# braille_keyboard.net
KiCad netlist of a schematic drawn in EAGLE
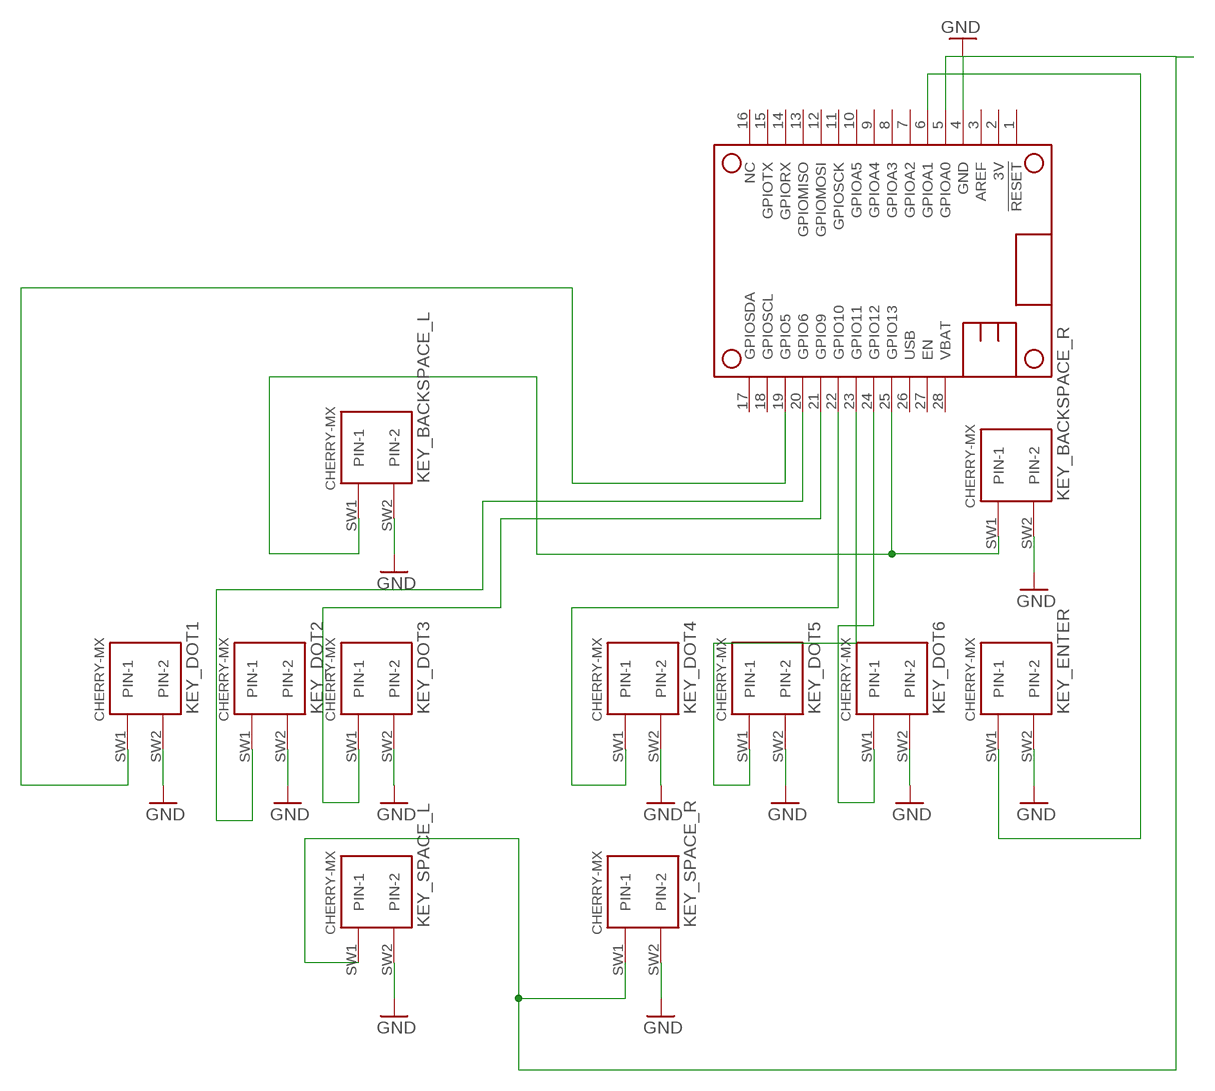
[diagram p0: schematic, sheet 1]

(export (version "E")
  (design (tool "Eeschema 10.0.6"))
  (components
    (comp (ref "KEY_BACKSPACE_L")
      (value "CHERRY-MX")
      (footprint "eagle-import:CHERRY-MX")
      (libsource (lib "eagle-import") (part "CHERRY-MX"))
    )
    (comp (ref "KEY_BACKSPACE_R")
      (value "CHERRY-MX")
      (footprint "eagle-import:CHERRY-MX")
      (libsource (lib "eagle-import") (part "CHERRY-MX"))
    )
    (comp (ref "KEY_DOT1")
      (value "CHERRY-MX")
      (footprint "eagle-import:CHERRY-MX")
      (libsource (lib "eagle-import") (part "CHERRY-MX"))
    )
    (comp (ref "KEY_DOT2")
      (value "CHERRY-MX")
      (footprint "eagle-import:CHERRY-MX")
      (libsource (lib "eagle-import") (part "CHERRY-MX"))
    )
    (comp (ref "KEY_DOT3")
      (value "CHERRY-MX")
      (footprint "eagle-import:CHERRY-MX")
      (libsource (lib "eagle-import") (part "CHERRY-MX"))
    )
    (comp (ref "KEY_DOT4")
      (value "CHERRY-MX")
      (footprint "eagle-import:CHERRY-MX")
      (libsource (lib "eagle-import") (part "CHERRY-MX"))
    )
    (comp (ref "KEY_DOT5")
      (value "CHERRY-MX")
      (footprint "eagle-import:CHERRY-MX")
      (libsource (lib "eagle-import") (part "CHERRY-MX"))
    )
    (comp (ref "KEY_DOT6")
      (value "CHERRY-MX")
      (footprint "eagle-import:CHERRY-MX")
      (libsource (lib "eagle-import") (part "CHERRY-MX"))
    )
    (comp (ref "KEY_ENTER")
      (value "CHERRY-MX")
      (footprint "eagle-import:CHERRY-MX")
      (libsource (lib "eagle-import") (part "CHERRY-MX"))
    )
    (comp (ref "KEY_SPACE_L")
      (value "CHERRY-MX")
      (footprint "eagle-import:CHERRY-MX")
      (libsource (lib "eagle-import") (part "CHERRY-MX"))
    )
    (comp (ref "KEY_SPACE_R")
      (value "CHERRY-MX")
      (footprint "eagle-import:CHERRY-MX")
      (libsource (lib "eagle-import") (part "CHERRY-MX"))
    )
    (comp (ref "MS1")
      (value "FEATHERWING")
      (footprint "eagle-import:FEATHERWING")
      (libsource (lib "eagle-import") (part "FEATHERWING"))
    )
  )
  (nets
    (net (code "1") (name "/3V") (class "Default")
      (node (ref "MS1") (pin "2") (pinfunction "3V_2") (pintype "power_in"))
    )
    (net (code "2") (name "/USB") (class "Default")
      (node (ref "MS1") (pin "26") (pinfunction "USB_26") (pintype "power_in"))
    )
    (net (code "3") (name "/VBAT") (class "Default")
      (node (ref "MS1") (pin "28") (pinfunction "VBAT_28") (pintype "power_in"))
    )
    (net (code "4") (name "GND") (class "Default")
      (node (ref "KEY_BACKSPACE_L") (pin "SW2") (pinfunction "PIN-2_SW2") (pintype "bidirectional"))
      (node (ref "KEY_BACKSPACE_R") (pin "SW2") (pinfunction "PIN-2_SW2") (pintype "bidirectional"))
      (node (ref "KEY_DOT1") (pin "SW2") (pinfunction "PIN-2_SW2") (pintype "bidirectional"))
      (node (ref "KEY_DOT2") (pin "SW2") (pinfunction "PIN-2_SW2") (pintype "bidirectional"))
      (node (ref "KEY_DOT3") (pin "SW2") (pinfunction "PIN-2_SW2") (pintype "bidirectional"))
      (node (ref "KEY_DOT4") (pin "SW2") (pinfunction "PIN-2_SW2") (pintype "bidirectional"))
      (node (ref "KEY_DOT5") (pin "SW2") (pinfunction "PIN-2_SW2") (pintype "bidirectional"))
      (node (ref "KEY_DOT6") (pin "SW2") (pinfunction "PIN-2_SW2") (pintype "bidirectional"))
      (node (ref "KEY_ENTER") (pin "SW2") (pinfunction "PIN-2_SW2") (pintype "bidirectional"))
      (node (ref "KEY_SPACE_L") (pin "SW2") (pinfunction "PIN-2_SW2") (pintype "bidirectional"))
      (node (ref "KEY_SPACE_R") (pin "SW2") (pinfunction "PIN-2_SW2") (pintype "bidirectional"))
      (node (ref "MS1") (pin "4") (pinfunction "GND_4") (pintype "power_in"))
    )
    (net (code "5") (name "Net-(KEY_BACKSPACE_L-PIN-1)") (class "Default")
      (node (ref "KEY_BACKSPACE_L") (pin "SW1") (pinfunction "PIN-1_SW1") (pintype "bidirectional"))
      (node (ref "KEY_BACKSPACE_R") (pin "SW1") (pinfunction "PIN-1_SW1") (pintype "bidirectional"))
      (node (ref "MS1") (pin "25") (pinfunction "GPIO13_25") (pintype "bidirectional"))
    )
    (net (code "6") (name "Net-(KEY_DOT1-PIN-1)") (class "Default")
      (node (ref "KEY_DOT1") (pin "SW1") (pinfunction "PIN-1_SW1") (pintype "bidirectional"))
      (node (ref "MS1") (pin "19") (pinfunction "GPIO5_19") (pintype "bidirectional"))
    )
    (net (code "7") (name "Net-(KEY_DOT2-PIN-1)") (class "Default")
      (node (ref "KEY_DOT2") (pin "SW1") (pinfunction "PIN-1_SW1") (pintype "bidirectional"))
      (node (ref "MS1") (pin "20") (pinfunction "GPIO6_20") (pintype "bidirectional"))
    )
    (net (code "8") (name "Net-(KEY_DOT3-PIN-1)") (class "Default")
      (node (ref "KEY_DOT3") (pin "SW1") (pinfunction "PIN-1_SW1") (pintype "bidirectional"))
      (node (ref "MS1") (pin "21") (pinfunction "GPIO9_21") (pintype "bidirectional"))
    )
    (net (code "9") (name "Net-(KEY_DOT4-PIN-1)") (class "Default")
      (node (ref "KEY_DOT4") (pin "SW1") (pinfunction "PIN-1_SW1") (pintype "bidirectional"))
      (node (ref "MS1") (pin "22") (pinfunction "GPIO10_22") (pintype "bidirectional"))
    )
    (net (code "10") (name "Net-(KEY_DOT5-PIN-1)") (class "Default")
      (node (ref "KEY_DOT5") (pin "SW1") (pinfunction "PIN-1_SW1") (pintype "bidirectional"))
      (node (ref "MS1") (pin "23") (pinfunction "GPIO11_23") (pintype "bidirectional"))
    )
    (net (code "11") (name "Net-(KEY_DOT6-PIN-1)") (class "Default")
      (node (ref "KEY_DOT6") (pin "SW1") (pinfunction "PIN-1_SW1") (pintype "bidirectional"))
      (node (ref "MS1") (pin "24") (pinfunction "GPIO12_24") (pintype "bidirectional"))
    )
    (net (code "12") (name "Net-(KEY_ENTER-PIN-1)") (class "Default")
      (node (ref "KEY_ENTER") (pin "SW1") (pinfunction "PIN-1_SW1") (pintype "bidirectional"))
      (node (ref "MS1") (pin "6") (pinfunction "GPIOA1_6") (pintype "bidirectional"))
    )
    (net (code "13") (name "Net-(KEY_SPACE_L-PIN-1)") (class "Default")
      (node (ref "KEY_SPACE_L") (pin "SW1") (pinfunction "PIN-1_SW1") (pintype "bidirectional"))
      (node (ref "KEY_SPACE_R") (pin "SW1") (pinfunction "PIN-1_SW1") (pintype "bidirectional"))
      (node (ref "MS1") (pin "5") (pinfunction "GPIOA0_5") (pintype "bidirectional"))
    )
    (net (code "14") (name "unconnected-(MS1-AREF-Pad3)") (class "Default")
      (node (ref "MS1") (pin "3") (pinfunction "AREF_3") (pintype "passive"))
    )
    (net (code "15") (name "unconnected-(MS1-EN-Pad27)") (class "Default")
      (node (ref "MS1") (pin "27") (pinfunction "EN_27") (pintype "passive"))
    )
    (net (code "16") (name "unconnected-(MS1-GPIOA2-Pad7)") (class "Default")
      (node (ref "MS1") (pin "7") (pinfunction "GPIOA2_7") (pintype "bidirectional"))
    )
    (net (code "17") (name "unconnected-(MS1-GPIOA3-Pad8)") (class "Default")
      (node (ref "MS1") (pin "8") (pinfunction "GPIOA3_8") (pintype "bidirectional"))
    )
    (net (code "18") (name "unconnected-(MS1-GPIOA4-Pad9)") (class "Default")
      (node (ref "MS1") (pin "9") (pinfunction "GPIOA4_9") (pintype "bidirectional"))
    )
    (net (code "19") (name "unconnected-(MS1-GPIOA5-Pad10)") (class "Default")
      (node (ref "MS1") (pin "10") (pinfunction "GPIOA5_10") (pintype "bidirectional"))
    )
    (net (code "20") (name "unconnected-(MS1-GPIOMISO-Pad13)") (class "Default")
      (node (ref "MS1") (pin "13") (pinfunction "GPIOMISO_13") (pintype "bidirectional"))
    )
    (net (code "21") (name "unconnected-(MS1-GPIOMOSI-Pad12)") (class "Default")
      (node (ref "MS1") (pin "12") (pinfunction "GPIOMOSI_12") (pintype "bidirectional"))
    )
    (net (code "22") (name "unconnected-(MS1-GPIORX-Pad14)") (class "Default")
      (node (ref "MS1") (pin "14") (pinfunction "GPIORX_14") (pintype "bidirectional"))
    )
    (net (code "23") (name "unconnected-(MS1-GPIOSCK-Pad11)") (class "Default")
      (node (ref "MS1") (pin "11") (pinfunction "GPIOSCK_11") (pintype "bidirectional"))
    )
    (net (code "24") (name "unconnected-(MS1-GPIOSCL-Pad18)") (class "Default")
      (node (ref "MS1") (pin "18") (pinfunction "GPIOSCL_18") (pintype "bidirectional"))
    )
    (net (code "25") (name "unconnected-(MS1-GPIOSDA-Pad17)") (class "Default")
      (node (ref "MS1") (pin "17") (pinfunction "GPIOSDA_17") (pintype "bidirectional"))
    )
    (net (code "26") (name "unconnected-(MS1-GPIOTX-Pad15)") (class "Default")
      (node (ref "MS1") (pin "15") (pinfunction "GPIOTX_15") (pintype "bidirectional"))
    )
    (net (code "27") (name "unconnected-(MS1-NC-Pad16)") (class "Default")
      (node (ref "MS1") (pin "16") (pinfunction "NC_16") (pintype "passive"))
    )
    (net (code "28") (name "unconnected-(MS1-~{RESET}-Pad1)") (class "Default")
      (node (ref "MS1") (pin "1") (pinfunction "~{RESET}_1") (pintype "input"))
    )
  )
)
